# RS485.net
KiCad netlist of a schematic drawn in Altium Designer
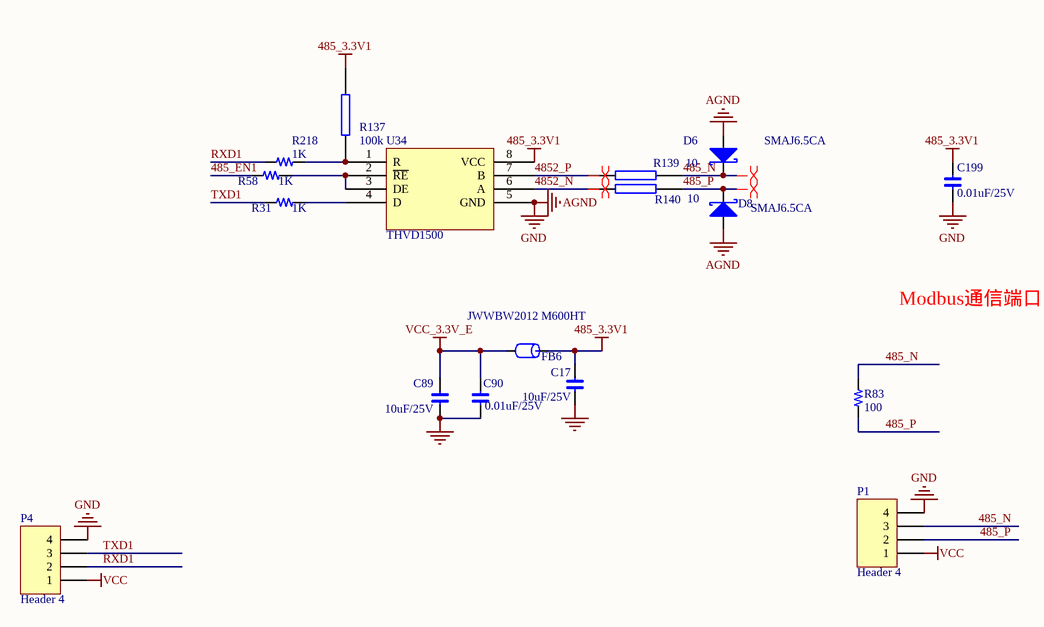
[diagram p0: RS485.SchDoc]

(export (version "E")
  (design (tool "Eeschema 10.0.6"))
  (components
    (comp (ref "C17")
      (value "10uF/25V")
      (footprint "0603C")
      (description "C")
      (libsource (lib "Schlib_20110825") (part "C"))
    )
    (comp (ref "C89")
      (value "10uF/25V")
      (footprint "0603C")
      (description "C")
      (libsource (lib "Schlib_20110825") (part "C"))
    )
    (comp (ref "C90")
      (value "0.01uF/25V")
      (footprint "0603C")
      (description "C")
      (libsource (lib "Schlib_20110825") (part "C"))
    )
    (comp (ref "C199")
      (value "0.01uF/25V")
      (footprint "0603C")
      (description "C")
      (libsource (lib "Schlib_20110825") (part "C"))
    )
    (comp (ref "D6")
      (value "SMAJ6.5CA")
      (footprint "SMA")
      (description "Schottky Diode")
      (libsource (lib "*") (part "DIODE S"))
    )
    (comp (ref "D8")
      (value "SMAJ6.5CA")
      (footprint "SMA")
      (description "Schottky Diode")
      (libsource (lib "*") (part "DIODE S"))
    )
    (comp (ref "FB6")
      (value "JWWBW2012 M600HT")
      (footprint "0805CZ")
      (libsource (lib "Schlib_20110825") (part "FB"))
    )
    (comp (ref "P1")
      (value "Header 4")
      (footprint "HDR1X4")
      (description "Header, 4-Pin")
      (fields (field (name "PUBLISHER") "Altium Limited"))
      (libsource (lib "Miscellaneous Connectors") (part "Header 4"))
    )
    (comp (ref "P4")
      (value "Header 4")
      (footprint "HDR1X4")
      (description "Header, 4-Pin")
      (fields (field (name "PUBLISHER") "Altium Limited"))
      (libsource (lib "Miscellaneous Connectors") (part "Header 4"))
    )
    (comp (ref "R31") (value "1K") (footprint "0603R") (description "R") (libsource (lib "JRJ_1") (part "R")))
    (comp (ref "R58") (value "1K") (footprint "0603R") (description "R") (libsource (lib "JRJ_1") (part "R")))
    (comp (ref "R83")
      (value "100")
      (footprint "0603R")
      (description "R")
      (libsource (lib "JRJ_1") (part "R"))
    )
    (comp (ref "R137") (value "100k") (footprint "0603R") (libsource (lib "*") (part "RES2")))
    (comp (ref "R139") (value "10") (footprint "1206R") (libsource (lib "*") (part "RES2")))
    (comp (ref "R140") (value "10") (footprint "1206R") (libsource (lib "*") (part "RES2")))
    (comp (ref "R218")
      (value "1K")
      (footprint "0603R")
      (description "R")
      (libsource (lib "JRJ_1") (part "R"))
    )
    (comp (ref "U34") (value "THVD1500") (footprint "so-8") (libsource (lib "Schlib1") (part "SN65HVD06D")))
  )
  (nets
    (net (code "1") (name "/485_EN1") (class "Default") (node (ref "R58") (pin "2") (pintype "passive")))
    (net (code "2") (name "/485_N") (class "Default")
      (node (ref "D6") (pin "2") (pinfunction "K_2") (pintype "passive"))
      (node (ref "P1") (pin "3") (pinfunction "3_3") (pintype "passive"))
      (node (ref "R139") (pin "1") (pinfunction "1_1") (pintype "passive"))
      (node (ref "R83") (pin "2") (pintype "passive"))
    )
    (net (code "3") (name "/485_P") (class "Default")
      (node (ref "D8") (pin "2") (pinfunction "K_2") (pintype "passive"))
      (node (ref "P1") (pin "2") (pinfunction "2_2") (pintype "passive"))
      (node (ref "R140") (pin "1") (pinfunction "1_1") (pintype "passive"))
      (node (ref "R83") (pin "1") (pintype "passive"))
    )
    (net (code "4") (name "/4852_N") (class "Default")
      (node (ref "R140") (pin "2") (pinfunction "2_2") (pintype "passive"))
      (node (ref "U34") (pin "6") (pinfunction "A_6") (pintype "passive"))
    )
    (net (code "5") (name "/4852_P") (class "Default")
      (node (ref "R139") (pin "2") (pinfunction "2_2") (pintype "passive"))
      (node (ref "U34") (pin "7") (pinfunction "B_7") (pintype "passive"))
    )
    (net (code "6") (name "/RXD1") (class "Default")
      (node (ref "P4") (pin "2") (pinfunction "2_2") (pintype "passive"))
      (node (ref "R218") (pin "2") (pintype "passive"))
    )
    (net (code "7") (name "/TXD1") (class "Default")
      (node (ref "P4") (pin "3") (pinfunction "3_3") (pintype "passive"))
      (node (ref "R31") (pin "2") (pintype "passive"))
    )
    (net (code "8") (name "485_3.3V1") (class "Default")
      (node (ref "C17") (pin "2") (pintype "passive"))
      (node (ref "C199") (pin "2") (pintype "passive"))
      (node (ref "FB6") (pin "1") (pintype "passive"))
      (node (ref "R137") (pin "2") (pinfunction "2_2") (pintype "passive"))
      (node (ref "U34") (pin "8") (pinfunction "VCC_8") (pintype "passive"))
    )
    (net (code "9") (name "AGND") (class "Default")
      (node (ref "C17") (pin "1") (pintype "passive"))
      (node (ref "C199") (pin "1") (pintype "passive"))
      (node (ref "C89") (pin "1") (pintype "passive"))
      (node (ref "C90") (pin "1") (pintype "passive"))
      (node (ref "D6") (pin "1") (pinfunction "A_1") (pintype "passive"))
      (node (ref "D8") (pin "1") (pinfunction "A_1") (pintype "passive"))
      (node (ref "P1") (pin "4") (pinfunction "4_4") (pintype "passive"))
      (node (ref "P4") (pin "4") (pinfunction "4_4") (pintype "passive"))
      (node (ref "U34") (pin "5") (pinfunction "GND_5") (pintype "passive"))
    )
    (net (code "10") (name "Net-(U34-D)") (class "Default")
      (node (ref "R31") (pin "1") (pintype "passive"))
      (node (ref "U34") (pin "4") (pinfunction "D_4") (pintype "passive"))
    )
    (net (code "11") (name "Net-(U34-DE)") (class "Default")
      (node (ref "R58") (pin "1") (pintype "passive"))
      (node (ref "U34") (pin "2") (pinfunction "~{RE}_2") (pintype "passive"))
      (node (ref "U34") (pin "3") (pinfunction "DE_3") (pintype "passive"))
    )
    (net (code "12") (name "Net-(U34-R)") (class "Default")
      (node (ref "R137") (pin "1") (pinfunction "1_1") (pintype "passive"))
      (node (ref "R218") (pin "1") (pintype "passive"))
      (node (ref "U34") (pin "1") (pinfunction "R_1") (pintype "passive"))
    )
    (net (code "13") (name "VCC") (class "Default")
      (node (ref "P1") (pin "1") (pinfunction "1_1") (pintype "passive"))
      (node (ref "P4") (pin "1") (pinfunction "1_1") (pintype "passive"))
    )
    (net (code "14") (name "VCC_3.3V_E") (class "Default")
      (node (ref "C89") (pin "2") (pintype "passive"))
      (node (ref "C90") (pin "2") (pintype "passive"))
      (node (ref "FB6") (pin "2") (pintype "passive"))
    )
  )
)
